# Channel.net
KiCad netlist of a schematic drawn in Altium Designer
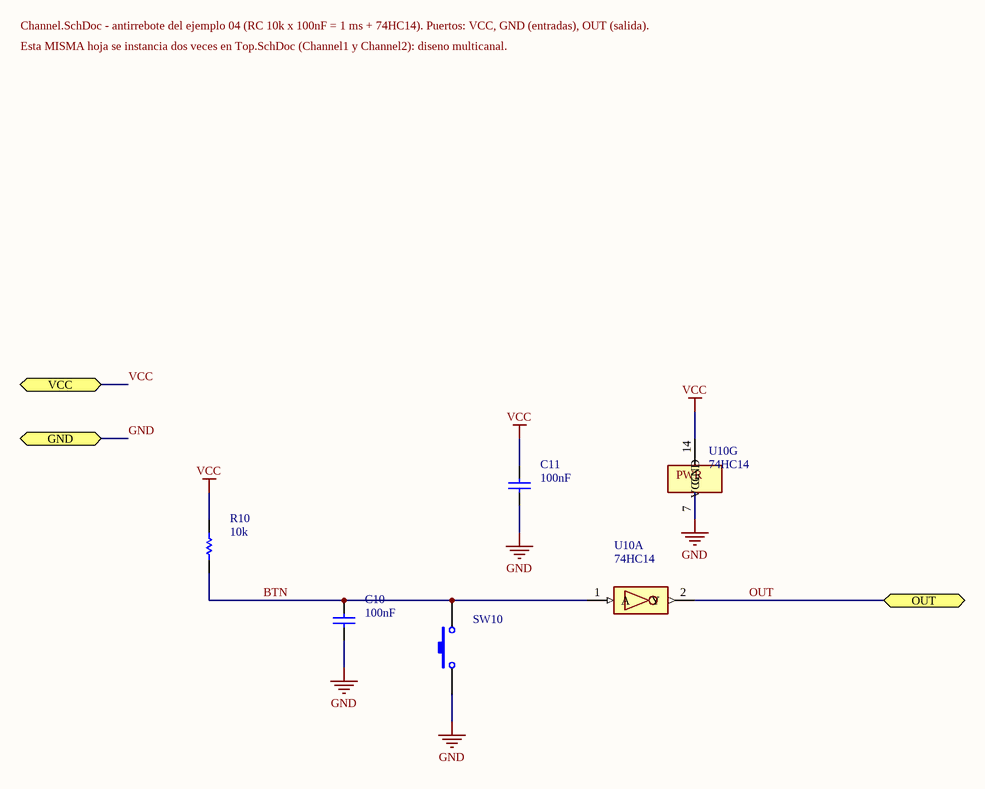
[diagram p0: Channel.SchDoc]

(export (version "E")
  (design (tool "Eeschema 10.0.6"))
  (components
    (comp (ref "C10")
      (value "100nF")
      (description "Capacitor 100 nF (debounce)")
      (fields
        (field (name "MANUFACTURER") "KEMET")
        (field (name "MANUFACTURER PART NUMBER") "C320C104K5R5TA")
        (field (name "PUBLISHER") "Altium Limited")
      )
      (libsource (lib "Miscellaneous Devices") (part "Cap"))
    )
    (comp (ref "C11")
      (value "100nF")
      (description "Capacitor 100 nF (desacople U10)")
      (fields
        (field (name "MANUFACTURER") "KEMET")
        (field (name "MANUFACTURER PART NUMBER") "C320C104K5R5TA")
        (field (name "PUBLISHER") "Altium Limited")
      )
      (libsource (lib "Miscellaneous Devices") (part "Cap"))
    )
    (comp (ref "R10")
      (value "10k")
      (description "Resistor 10 kohm (pull-up)")
      (fields
        (field (name "MANUFACTURER") "Yageo")
        (field (name "MANUFACTURER PART NUMBER") "CFR-25JB-52-10K")
        (field (name "PUBLISHER") "Altium Limited")
      )
      (libsource (lib "Miscellaneous Devices") (part "Res1"))
    )
    (comp (ref "SW10")
      (value "SW-PB")
      (description "Pulsador normalmente abierto")
      (fields
        (field (name "MANUFACTURER") "Generic")
        (field (name "MANUFACTURER PART NUMBER") "Tactile 6x6")
        (field (name "PUBLISHER") "Altium Limited")
      )
      (libsource (lib "Miscellaneous Devices") (part "SW-PB"))
    )
    (comp (ref "U10")
      (value "74HC14")
      (footprint "DIP-14")
      (description "Hex Schmitt-trigger inverter, 6 gates (A-F) + power part G (VCC=14, GND=7)")
      (fields
        (field (name "MANUFACTURER") "Texas Instruments")
        (field (name "MANUFACTURER PART NUMBER") "SN74HC14N")
      )
      (libsource (lib "*") (part "74HC14"))
    )
  )
  (nets
    (net (code "1") (name "/BTN") (class "Default")
      (node (ref "C10") (pin "2") (pinfunction "2_2") (pintype "passive"))
      (node (ref "R10") (pin "1") (pinfunction "1_1") (pintype "passive"))
      (node (ref "SW10") (pin "2") (pinfunction "2_2") (pintype "passive"))
      (node (ref "U10") (pin "1") (pinfunction "A_1") (pintype "input"))
    )
    (net (code "2") (name "/OUT") (class "Default")
      (node (ref "U10") (pin "2") (pinfunction "Y_2") (pintype "output"))
    )
    (net (code "3") (name "GND") (class "Default")
      (node (ref "C10") (pin "1") (pinfunction "1_1") (pintype "passive"))
      (node (ref "C11") (pin "1") (pinfunction "1_1") (pintype "passive"))
      (node (ref "SW10") (pin "1") (pinfunction "1_1") (pintype "passive"))
      (node (ref "U10") (pin "7") (pinfunction "GND_7") (pintype "power_in"))
    )
    (net (code "4") (name "VCC") (class "Default")
      (node (ref "C11") (pin "2") (pinfunction "2_2") (pintype "passive"))
      (node (ref "R10") (pin "2") (pinfunction "2_2") (pintype "passive"))
      (node (ref "U10") (pin "14") (pinfunction "VCC_14") (pintype "power_in"))
    )
  )
)
